# 1_POWER.net
KiCad netlist of a schematic drawn in Altium Designer
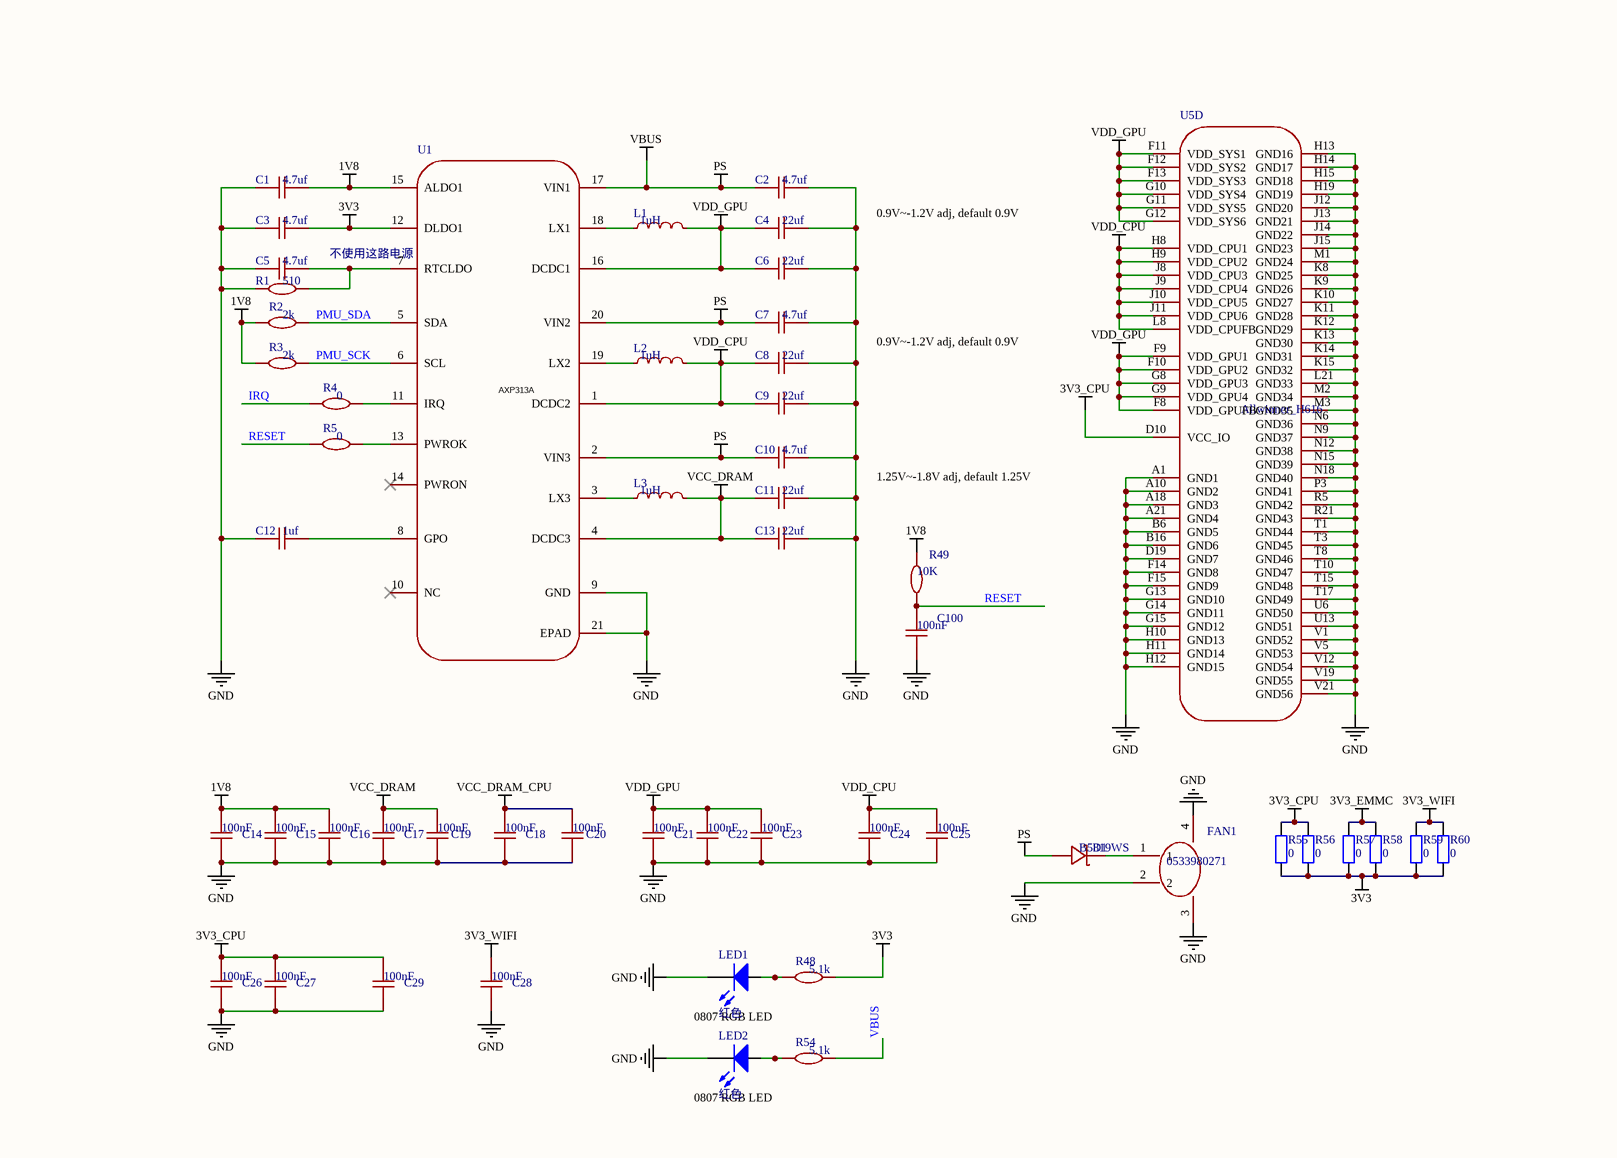
[diagram p0: 1_POWER.schdoc]

(export (version "E")
  (design (tool "Eeschema 10.0.6"))
  (components
    (comp (ref "C1")
      (value "4.7uf")
      (footprint "PCB:C0402")
      (libsource (lib "PCB_Project") (part "CAP_0402"))
    )
    (comp (ref "C2")
      (value "4.7uf")
      (footprint "PCB:C0603")
      (libsource (lib "PCB_Project") (part "CAP_0603"))
    )
    (comp (ref "C3")
      (value "4.7uf")
      (footprint "PCB:C0402")
      (libsource (lib "PCB_Project") (part "CAP_0402"))
    )
    (comp (ref "C4") (value "22uf") (footprint "PCB:C0603") (libsource (lib "PCB_Project") (part "CAP_0603")))
    (comp (ref "C5")
      (value "4.7uf")
      (footprint "PCB:C0402")
      (libsource (lib "PCB_Project") (part "CAP_0402"))
    )
    (comp (ref "C6") (value "22uf") (footprint "PCB:C0603") (libsource (lib "PCB_Project") (part "CAP_0603")))
    (comp (ref "C7")
      (value "4.7uf")
      (footprint "PCB:C0603")
      (libsource (lib "PCB_Project") (part "CAP_0603"))
    )
    (comp (ref "C8") (value "22uf") (footprint "PCB:C0603") (libsource (lib "PCB_Project") (part "CAP_0603")))
    (comp (ref "C9") (value "22uf") (footprint "PCB:C0603") (libsource (lib "PCB_Project") (part "CAP_0603")))
    (comp (ref "C10")
      (value "4.7uf")
      (footprint "PCB:C0603")
      (libsource (lib "PCB_Project") (part "CAP_0603"))
    )
    (comp (ref "C11")
      (value "22uf")
      (footprint "PCB:C0603")
      (libsource (lib "PCB_Project") (part "CAP_0603"))
    )
    (comp (ref "C12") (value "1uf") (footprint "PCB:C0402") (libsource (lib "PCB_Project") (part "CAP_0402")))
    (comp (ref "C13")
      (value "22uf")
      (footprint "PCB:C0603")
      (libsource (lib "PCB_Project") (part "CAP_0603"))
    )
    (comp (ref "C14")
      (value "100nF")
      (footprint "PCB:C0402-NSK")
      (libsource (lib "PCB_Project") (part "CAP_0402"))
    )
    (comp (ref "C15")
      (value "100nF")
      (footprint "PCB:C0402-NSK")
      (libsource (lib "PCB_Project") (part "CAP_0402"))
    )
    (comp (ref "C16")
      (value "100nF")
      (footprint "PCB:C0402-NSK")
      (libsource (lib "PCB_Project") (part "CAP_0402"))
    )
    (comp (ref "C17")
      (value "100nF")
      (footprint "PCB:C0402-NSK")
      (libsource (lib "PCB_Project") (part "CAP_0402"))
    )
    (comp (ref "C18")
      (value "100nF")
      (footprint "PCB:C0402-NSK")
      (libsource (lib "PCB_Project") (part "CAP_0402"))
    )
    (comp (ref "C19")
      (value "100nF")
      (footprint "PCB:C0402-NSK")
      (libsource (lib "PCB_Project") (part "CAP_0402"))
    )
    (comp (ref "C20")
      (value "100nF")
      (footprint "PCB:C0402-NSK")
      (libsource (lib "PCB_Project") (part "CAP_0402"))
    )
    (comp (ref "C21")
      (value "100nF")
      (footprint "PCB:C0402-NSK")
      (libsource (lib "PCB_Project") (part "CAP_0402"))
    )
    (comp (ref "C22")
      (value "100nF")
      (footprint "PCB:C0402-NSK")
      (libsource (lib "PCB_Project") (part "CAP_0402"))
    )
    (comp (ref "C23")
      (value "100nF")
      (footprint "PCB:C0402-NSK")
      (libsource (lib "PCB_Project") (part "CAP_0402"))
    )
    (comp (ref "C24")
      (value "100nF")
      (footprint "PCB:C0402-NSK")
      (libsource (lib "PCB_Project") (part "CAP_0402"))
    )
    (comp (ref "C25")
      (value "100nF")
      (footprint "PCB:C0402-NSK")
      (libsource (lib "PCB_Project") (part "CAP_0402"))
    )
    (comp (ref "C26")
      (value "100nF")
      (footprint "PCB:C0402-NSK")
      (libsource (lib "PCB_Project") (part "CAP_0402"))
    )
    (comp (ref "C27")
      (value "100nF")
      (footprint "PCB:C0402-NSK")
      (libsource (lib "PCB_Project") (part "CAP_0402"))
    )
    (comp (ref "C28")
      (value "100nF")
      (footprint "PCB:C0402-NSK")
      (libsource (lib "PCB_Project") (part "CAP_0402"))
    )
    (comp (ref "C29")
      (value "100nF")
      (footprint "PCB:C0402-NSK")
      (libsource (lib "PCB_Project") (part "CAP_0402"))
    )
    (comp (ref "C100")
      (value "100nF")
      (footprint "PCB:C0402")
      (libsource (lib "PCB_Project") (part "CAP_0402"))
    )
    (comp (ref "D1")
      (value "B5819WS")
      (footprint "PCB:SOD-323_L1.8-W1.3-LS2.5-NSK")
      (libsource (lib "PCB_Project") (part "B5819WS"))
    )
    (comp (ref "FAN1")
      (value "0533980271")
      (footprint "PCB:CONN-SMD_2P-P1.25_053398-0X71")
      (libsource (lib "PCB_Project") (part "0533980271"))
    )
    (comp (ref "L1")
      (value "1uH")
      (footprint "PCB:IND-SMD_L2.0-W1.6_1")
      (libsource (lib "PCB_Project") (part "CKCS201610-2.2uH/M_2"))
    )
    (comp (ref "L2")
      (value "1uH")
      (footprint "PCB:IND-SMD_L2.0-W1.6_1")
      (libsource (lib "PCB_Project") (part "CKCS201610-2.2uH/M_2"))
    )
    (comp (ref "L3")
      (value "1uH")
      (footprint "PCB:IND-SMD_L2.0-W1.6_1")
      (libsource (lib "PCB_Project") (part "CKCS201610-2.2uH/M_2"))
    )
    (comp (ref "LED1")
      (value "红色")
      (footprint "PCB:LED0805_G")
      (description "贴片LED")
      (libsource (lib "PCB_Project") (part "LED"))
    )
    (comp (ref "LED2")
      (value "红色")
      (footprint "PCB:LED0805_G")
      (description "贴片LED")
      (libsource (lib "PCB_Project") (part "LED"))
    )
    (comp (ref "R1")
      (value "510")
      (footprint "PCB:R0402-NSK_2")
      (libsource (lib "PCB_Project") (part "Res_0402"))
    )
    (comp (ref "R2")
      (value "2k")
      (footprint "PCB:R0402-NSK_2")
      (libsource (lib "PCB_Project") (part "Res_0402"))
    )
    (comp (ref "R3")
      (value "2k")
      (footprint "PCB:R0402-NSK_2")
      (libsource (lib "PCB_Project") (part "Res_0402"))
    )
    (comp (ref "R4")
      (value "0")
      (footprint "PCB:R0402-NSK_2")
      (libsource (lib "PCB_Project") (part "Res_0402"))
    )
    (comp (ref "R5")
      (value "0")
      (footprint "PCB:R0402-NSK_2")
      (libsource (lib "PCB_Project") (part "Res_0402"))
    )
    (comp (ref "R48")
      (value "5.1k")
      (footprint "PCB:R0402-NSK_2")
      (libsource (lib "PCB_Project") (part "Res_0402"))
    )
    (comp (ref "R49")
      (value "10K")
      (footprint "PCB:R0402-NSK_2")
      (libsource (lib "PCB_Project") (part "Res_0402"))
    )
    (comp (ref "R54")
      (value "5.1k")
      (footprint "PCB:R0402-NSK_2")
      (libsource (lib "PCB_Project") (part "Res_0402"))
    )
    (comp (ref "R55")
      (value "0")
      (footprint "PCB:R0805_L")
      (description "贴片电阻")
      (libsource (lib "PCB_Project") (part "R"))
    )
    (comp (ref "R56")
      (value "0")
      (footprint "PCB:R0805_L")
      (description "贴片电阻")
      (libsource (lib "PCB_Project") (part "R"))
    )
    (comp (ref "R57")
      (value "0")
      (footprint "PCB:R0805_L")
      (description "贴片电阻")
      (libsource (lib "PCB_Project") (part "R"))
    )
    (comp (ref "R58")
      (value "0")
      (footprint "PCB:R0805_L")
      (description "贴片电阻")
      (libsource (lib "PCB_Project") (part "R"))
    )
    (comp (ref "R59")
      (value "0")
      (footprint "PCB:R0805_L")
      (description "贴片电阻")
      (libsource (lib "PCB_Project") (part "R"))
    )
    (comp (ref "R60")
      (value "0")
      (footprint "PCB:R0805_L")
      (description "贴片电阻")
      (libsource (lib "PCB_Project") (part "R"))
    )
    (comp (ref "U1")
      (value "AXP313A")
      (footprint "PCB:WQFN-20_L3.0-W3.0-P0.40-BL-EP")
      (libsource (lib "PCB_Project") (part "AXP1530"))
    )
    (comp (ref "U5")
      (value "Allwinner_H616")
      (footprint "PCB:BGA284P65B1200_1400H125")
      (libsource (lib "PCB_Project") (part "Allwinner_H616"))
    )
  )
  (nets
    (net (code "1") (name "/IRQ") (class "Default")
      (node (ref "R4") (pin "1") (pinfunction "1_1") (pintype "passive"))
    )
    (net (code "2") (name "/PMU_SCK") (class "Default")
      (node (ref "R3") (pin "2") (pinfunction "2_2") (pintype "passive"))
      (node (ref "U1") (pin "6") (pinfunction "SCL_6") (pintype "passive"))
    )
    (net (code "3") (name "/PMU_SDA") (class "Default")
      (node (ref "R2") (pin "2") (pinfunction "2_2") (pintype "passive"))
      (node (ref "U1") (pin "5") (pinfunction "SDA_5") (pintype "passive"))
    )
    (net (code "4") (name "/RESET") (class "Default")
      (node (ref "C100") (pin "2") (pinfunction "2_2") (pintype "passive"))
      (node (ref "R49") (pin "1") (pinfunction "1_1") (pintype "passive"))
      (node (ref "R5") (pin "1") (pinfunction "1_1") (pintype "passive"))
    )
    (net (code "5") (name "1V8") (class "Default")
      (node (ref "C1") (pin "2") (pinfunction "2_2") (pintype "passive"))
      (node (ref "C14") (pin "2") (pinfunction "2_2") (pintype "passive"))
      (node (ref "C15") (pin "2") (pinfunction "2_2") (pintype "passive"))
      (node (ref "C16") (pin "2") (pinfunction "2_2") (pintype "passive"))
      (node (ref "R2") (pin "1") (pinfunction "1_1") (pintype "passive"))
      (node (ref "R3") (pin "1") (pinfunction "1_1") (pintype "passive"))
      (node (ref "R49") (pin "2") (pinfunction "2_2") (pintype "passive"))
      (node (ref "U1") (pin "15") (pinfunction "ALDO1_15") (pintype "passive"))
    )
    (net (code "6") (name "3V3") (class "Default")
      (node (ref "C3") (pin "2") (pinfunction "2_2") (pintype "passive"))
      (node (ref "R48") (pin "2") (pinfunction "2_2") (pintype "passive"))
      (node (ref "R55") (pin "1") (pinfunction "1_1") (pintype "passive"))
      (node (ref "R56") (pin "1") (pinfunction "1_1") (pintype "passive"))
      (node (ref "R57") (pin "1") (pinfunction "1_1") (pintype "passive"))
      (node (ref "R58") (pin "1") (pinfunction "1_1") (pintype "passive"))
      (node (ref "R59") (pin "1") (pinfunction "1_1") (pintype "passive"))
      (node (ref "R60") (pin "1") (pinfunction "1_1") (pintype "passive"))
      (node (ref "U1") (pin "12") (pinfunction "DLDO1_12") (pintype "passive"))
    )
    (net (code "7") (name "3V3_CPU") (class "Default")
      (node (ref "C26") (pin "2") (pinfunction "2_2") (pintype "passive"))
      (node (ref "C27") (pin "2") (pinfunction "2_2") (pintype "passive"))
      (node (ref "C29") (pin "2") (pinfunction "2_2") (pintype "passive"))
      (node (ref "R55") (pin "2") (pinfunction "2_2") (pintype "passive"))
      (node (ref "R56") (pin "2") (pinfunction "2_2") (pintype "passive"))
      (node (ref "U5") (pin "D10") (pinfunction "VCC_IO_D10") (pintype "passive"))
    )
    (net (code "8") (name "3V3_EMMC") (class "Default")
      (node (ref "R57") (pin "2") (pinfunction "2_2") (pintype "passive"))
      (node (ref "R58") (pin "2") (pinfunction "2_2") (pintype "passive"))
    )
    (net (code "9") (name "3V3_WIFI") (class "Default")
      (node (ref "C28") (pin "2") (pinfunction "2_2") (pintype "passive"))
      (node (ref "R59") (pin "2") (pinfunction "2_2") (pintype "passive"))
      (node (ref "R60") (pin "2") (pinfunction "2_2") (pintype "passive"))
    )
    (net (code "10") (name "GND") (class "Default")
      (node (ref "C1") (pin "1") (pinfunction "1_1") (pintype "passive"))
      (node (ref "C10") (pin "2") (pinfunction "2_2") (pintype "passive"))
      (node (ref "C100") (pin "1") (pinfunction "1_1") (pintype "passive"))
      (node (ref "C11") (pin "2") (pinfunction "2_2") (pintype "passive"))
      (node (ref "C12") (pin "1") (pinfunction "1_1") (pintype "passive"))
      (node (ref "C13") (pin "2") (pinfunction "2_2") (pintype "passive"))
      (node (ref "C14") (pin "1") (pinfunction "1_1") (pintype "passive"))
      (node (ref "C15") (pin "1") (pinfunction "1_1") (pintype "passive"))
      (node (ref "C16") (pin "1") (pinfunction "1_1") (pintype "passive"))
      (node (ref "C17") (pin "1") (pinfunction "1_1") (pintype "passive"))
      (node (ref "C18") (pin "1") (pinfunction "1_1") (pintype "passive"))
      (node (ref "C19") (pin "1") (pinfunction "1_1") (pintype "passive"))
      (node (ref "C2") (pin "2") (pinfunction "2_2") (pintype "passive"))
      (node (ref "C20") (pin "1") (pinfunction "1_1") (pintype "passive"))
      (node (ref "C21") (pin "1") (pinfunction "1_1") (pintype "passive"))
      (node (ref "C22") (pin "1") (pinfunction "1_1") (pintype "passive"))
      (node (ref "C23") (pin "1") (pinfunction "1_1") (pintype "passive"))
      (node (ref "C24") (pin "1") (pinfunction "1_1") (pintype "passive"))
      (node (ref "C25") (pin "1") (pinfunction "1_1") (pintype "passive"))
      (node (ref "C26") (pin "1") (pinfunction "1_1") (pintype "passive"))
      (node (ref "C27") (pin "1") (pinfunction "1_1") (pintype "passive"))
      (node (ref "C28") (pin "1") (pinfunction "1_1") (pintype "passive"))
      (node (ref "C29") (pin "1") (pinfunction "1_1") (pintype "passive"))
      (node (ref "C3") (pin "1") (pinfunction "1_1") (pintype "passive"))
      (node (ref "C4") (pin "2") (pinfunction "2_2") (pintype "passive"))
      (node (ref "C5") (pin "1") (pinfunction "1_1") (pintype "passive"))
      (node (ref "C6") (pin "2") (pinfunction "2_2") (pintype "passive"))
      (node (ref "C7") (pin "2") (pinfunction "2_2") (pintype "passive"))
      (node (ref "C8") (pin "2") (pinfunction "2_2") (pintype "passive"))
      (node (ref "C9") (pin "2") (pinfunction "2_2") (pintype "passive"))
      (node (ref "FAN1") (pin "2") (pinfunction "2_2") (pintype "passive"))
      (node (ref "FAN1") (pin "3") (pinfunction "3_3") (pintype "passive"))
      (node (ref "FAN1") (pin "4") (pinfunction "4_4") (pintype "passive"))
      (node (ref "LED1") (pin "2") (pinfunction "K_2") (pintype "passive"))
      (node (ref "LED2") (pin "2") (pinfunction "K_2") (pintype "passive"))
      (node (ref "R1") (pin "1") (pinfunction "1_1") (pintype "passive"))
      (node (ref "U1") (pin "21") (pinfunction "EPAD_21") (pintype "passive"))
      (node (ref "U1") (pin "9") (pinfunction "GND_9") (pintype "passive"))
      (node (ref "U5") (pin "A1") (pinfunction "GND1_A1") (pintype "passive"))
      (node (ref "U5") (pin "A10") (pinfunction "GND2_A10") (pintype "passive"))
      (node (ref "U5") (pin "A18") (pinfunction "GND3_A18") (pintype "passive"))
      (node (ref "U5") (pin "A21") (pinfunction "GND4_A21") (pintype "passive"))
      (node (ref "U5") (pin "B16") (pinfunction "GND6_B16") (pintype "passive"))
      (node (ref "U5") (pin "B6") (pinfunction "GND5_B6") (pintype "passive"))
      (node (ref "U5") (pin "D19") (pinfunction "GND7_D19") (pintype "passive"))
      (node (ref "U5") (pin "F14") (pinfunction "GND8_F14") (pintype "passive"))
      (node (ref "U5") (pin "F15") (pinfunction "GND9_F15") (pintype "passive"))
      (node (ref "U5") (pin "G13") (pinfunction "GND10_G13") (pintype "passive"))
      (node (ref "U5") (pin "G14") (pinfunction "GND11_G14") (pintype "passive"))
      (node (ref "U5") (pin "G15") (pinfunction "GND12_G15") (pintype "passive"))
      (node (ref "U5") (pin "H10") (pinfunction "GND13_H10") (pintype "passive"))
      (node (ref "U5") (pin "H11") (pinfunction "GND14_H11") (pintype "passive"))
      (node (ref "U5") (pin "H12") (pinfunction "GND15_H12") (pintype "passive"))
      (node (ref "U5") (pin "H13") (pinfunction "GND16_H13") (pintype "passive"))
      (node (ref "U5") (pin "H14") (pinfunction "GND17_H14") (pintype "passive"))
      (node (ref "U5") (pin "H15") (pinfunction "GND18_H15") (pintype "passive"))
      (node (ref "U5") (pin "H19") (pinfunction "GND19_H19") (pintype "passive"))
      (node (ref "U5") (pin "J12") (pinfunction "GND20_J12") (pintype "passive"))
      (node (ref "U5") (pin "J13") (pinfunction "GND21_J13") (pintype "passive"))
      (node (ref "U5") (pin "J14") (pinfunction "GND22_J14") (pintype "passive"))
      (node (ref "U5") (pin "J15") (pinfunction "GND23_J15") (pintype "passive"))
      (node (ref "U5") (pin "K10") (pinfunction "GND27_K10") (pintype "passive"))
      (node (ref "U5") (pin "K11") (pinfunction "GND28_K11") (pintype "passive"))
      (node (ref "U5") (pin "K12") (pinfunction "GND29_K12") (pintype "passive"))
      (node (ref "U5") (pin "K13") (pinfunction "GND30_K13") (pintype "passive"))
      (node (ref "U5") (pin "K14") (pinfunction "GND31_K14") (pintype "passive"))
      (node (ref "U5") (pin "K15") (pinfunction "GND32_K15") (pintype "passive"))
      (node (ref "U5") (pin "K8") (pinfunction "GND25_K8") (pintype "passive"))
      (node (ref "U5") (pin "K9") (pinfunction "GND26_K9") (pintype "passive"))
      (node (ref "U5") (pin "L21") (pinfunction "GND33_L21") (pintype "passive"))
      (node (ref "U5") (pin "M1") (pinfunction "GND24_M1") (pintype "passive"))
      (node (ref "U5") (pin "M2") (pinfunction "GND34_M2") (pintype "passive"))
      (node (ref "U5") (pin "M3") (pinfunction "GND35_M3") (pintype "passive"))
      (node (ref "U5") (pin "N12") (pinfunction "GND38_N12") (pintype "passive"))
      (node (ref "U5") (pin "N15") (pinfunction "GND39_N15") (pintype "passive"))
      (node (ref "U5") (pin "N18") (pinfunction "GND40_N18") (pintype "passive"))
      (node (ref "U5") (pin "N6") (pinfunction "GND36_N6") (pintype "passive"))
      (node (ref "U5") (pin "N9") (pinfunction "GND37_N9") (pintype "passive"))
      (node (ref "U5") (pin "P3") (pinfunction "GND41_P3") (pintype "passive"))
      (node (ref "U5") (pin "R21") (pinfunction "GND43_R21") (pintype "passive"))
      (node (ref "U5") (pin "R5") (pinfunction "GND42_R5") (pintype "passive"))
      (node (ref "U5") (pin "T1") (pinfunction "GND44_T1") (pintype "passive"))
      (node (ref "U5") (pin "T10") (pinfunction "GND47_T10") (pintype "passive"))
      (node (ref "U5") (pin "T15") (pinfunction "GND48_T15") (pintype "passive"))
      (node (ref "U5") (pin "T17") (pinfunction "GND49_T17") (pintype "passive"))
      (node (ref "U5") (pin "T3") (pinfunction "GND45_T3") (pintype "passive"))
      (node (ref "U5") (pin "T8") (pinfunction "GND46_T8") (pintype "passive"))
      (node (ref "U5") (pin "U13") (pinfunction "GND51_U13") (pintype "passive"))
      (node (ref "U5") (pin "U6") (pinfunction "GND50_U6") (pintype "passive"))
      (node (ref "U5") (pin "V1") (pinfunction "GND52_V1") (pintype "passive"))
      (node (ref "U5") (pin "V12") (pinfunction "GND54_V12") (pintype "passive"))
      (node (ref "U5") (pin "V19") (pinfunction "GND55_V19") (pintype "passive"))
      (node (ref "U5") (pin "V21") (pinfunction "GND56_V21") (pintype "passive"))
      (node (ref "U5") (pin "V5") (pinfunction "GND53_V5") (pintype "passive"))
    )
    (net (code "11") (name "Net-(D1-K)") (class "Default")
      (node (ref "D1") (pin "1") (pinfunction "K_1") (pintype "passive"))
      (node (ref "FAN1") (pin "1") (pinfunction "1_1") (pintype "passive"))
    )
    (net (code "12") (name "Net-(LED1-A)") (class "Default")
      (node (ref "LED1") (pin "1") (pinfunction "A_1") (pintype "passive"))
      (node (ref "R48") (pin "1") (pinfunction "1_1") (pintype "passive"))
    )
    (net (code "13") (name "Net-(LED2-A)") (class "Default")
      (node (ref "LED2") (pin "1") (pinfunction "A_1") (pintype "passive"))
      (node (ref "R54") (pin "1") (pinfunction "1_1") (pintype "passive"))
    )
    (net (code "14") (name "Net-(U1-GPO)") (class "Default")
      (node (ref "C12") (pin "2") (pinfunction "2_2") (pintype "passive"))
      (node (ref "U1") (pin "8") (pinfunction "GPO_8") (pintype "passive"))
    )
    (net (code "15") (name "Net-(U1-IRQ)") (class "Default")
      (node (ref "R4") (pin "2") (pinfunction "2_2") (pintype "passive"))
      (node (ref "U1") (pin "11") (pinfunction "IRQ_11") (pintype "passive"))
    )
    (net (code "16") (name "Net-(U1-LX1)") (class "Default")
      (node (ref "L1") (pin "1") (pinfunction "1_1") (pintype "passive"))
      (node (ref "U1") (pin "18") (pinfunction "LX1_18") (pintype "passive"))
    )
    (net (code "17") (name "Net-(U1-LX2)") (class "Default")
      (node (ref "L2") (pin "1") (pinfunction "1_1") (pintype "passive"))
      (node (ref "U1") (pin "19") (pinfunction "LX2_19") (pintype "passive"))
    )
    (net (code "18") (name "Net-(U1-LX3)") (class "Default")
      (node (ref "L3") (pin "1") (pinfunction "1_1") (pintype "passive"))
      (node (ref "U1") (pin "3") (pinfunction "LX3_3") (pintype "passive"))
    )
    (net (code "19") (name "Net-(U1-PWROK)") (class "Default")
      (node (ref "R5") (pin "2") (pinfunction "2_2") (pintype "passive"))
      (node (ref "U1") (pin "13") (pinfunction "PWROK_13") (pintype "passive"))
    )
    (net (code "20") (name "Net-(U1-RTCLDO)") (class "Default")
      (node (ref "C5") (pin "2") (pinfunction "2_2") (pintype "passive"))
      (node (ref "R1") (pin "2") (pinfunction "2_2") (pintype "passive"))
      (node (ref "U1") (pin "7") (pinfunction "RTCLDO_7") (pintype "passive"))
    )
    (net (code "21") (name "PS") (class "Default")
      (node (ref "C10") (pin "1") (pinfunction "1_1") (pintype "passive"))
      (node (ref "C2") (pin "1") (pinfunction "1_1") (pintype "passive"))
      (node (ref "C7") (pin "1") (pinfunction "1_1") (pintype "passive"))
      (node (ref "D1") (pin "2") (pinfunction "A_2") (pintype "passive"))
      (node (ref "R54") (pin "2") (pinfunction "2_2") (pintype "passive"))
      (node (ref "U1") (pin "17") (pinfunction "VIN1_17") (pintype "passive"))
      (node (ref "U1") (pin "2") (pinfunction "VIN3_2") (pintype "passive"))
      (node (ref "U1") (pin "20") (pinfunction "VIN2_20") (pintype "passive"))
    )
    (net (code "22") (name "VCC_DRAM") (class "Default")
      (node (ref "C11") (pin "1") (pinfunction "1_1") (pintype "passive"))
      (node (ref "C13") (pin "1") (pinfunction "1_1") (pintype "passive"))
      (node (ref "C17") (pin "2") (pinfunction "2_2") (pintype "passive"))
      (node (ref "C19") (pin "2") (pinfunction "2_2") (pintype "passive"))
      (node (ref "L3") (pin "2") (pinfunction "2_2") (pintype "passive"))
      (node (ref "U1") (pin "4") (pinfunction "DCDC3_4") (pintype "passive"))
    )
    (net (code "23") (name "VCC_DRAM_CPU") (class "Default")
      (node (ref "C18") (pin "2") (pinfunction "2_2") (pintype "passive"))
      (node (ref "C20") (pin "2") (pinfunction "2_2") (pintype "passive"))
    )
    (net (code "24") (name "VDD_CPU") (class "Default")
      (node (ref "C24") (pin "2") (pinfunction "2_2") (pintype "passive"))
      (node (ref "C25") (pin "2") (pinfunction "2_2") (pintype "passive"))
      (node (ref "C8") (pin "1") (pinfunction "1_1") (pintype "passive"))
      (node (ref "C9") (pin "1") (pinfunction "1_1") (pintype "passive"))
      (node (ref "L2") (pin "2") (pinfunction "2_2") (pintype "passive"))
      (node (ref "U1") (pin "1") (pinfunction "DCDC2_1") (pintype "passive"))
      (node (ref "U5") (pin "H8") (pinfunction "VDD_CPU1_H8") (pintype "passive"))
      (node (ref "U5") (pin "H9") (pinfunction "VDD_CPU2_H9") (pintype "passive"))
      (node (ref "U5") (pin "J10") (pinfunction "VDD_CPU5_J10") (pintype "passive"))
      (node (ref "U5") (pin "J11") (pinfunction "VDD_CPU6_J11") (pintype "passive"))
      (node (ref "U5") (pin "J8") (pinfunction "VDD_CPU3_J8") (pintype "passive"))
      (node (ref "U5") (pin "J9") (pinfunction "VDD_CPU4_J9") (pintype "passive"))
      (node (ref "U5") (pin "L8") (pinfunction "VDD_CPUFB_L8") (pintype "passive"))
    )
    (net (code "25") (name "VDD_GPU") (class "Default")
      (node (ref "C21") (pin "2") (pinfunction "2_2") (pintype "passive"))
      (node (ref "C22") (pin "2") (pinfunction "2_2") (pintype "passive"))
      (node (ref "C23") (pin "2") (pinfunction "2_2") (pintype "passive"))
      (node (ref "C4") (pin "1") (pinfunction "1_1") (pintype "passive"))
      (node (ref "C6") (pin "1") (pinfunction "1_1") (pintype "passive"))
      (node (ref "L1") (pin "2") (pinfunction "2_2") (pintype "passive"))
      (node (ref "U1") (pin "16") (pinfunction "DCDC1_16") (pintype "passive"))
      (node (ref "U5") (pin "F10") (pinfunction "VDD_GPU2_F10") (pintype "passive"))
      (node (ref "U5") (pin "F11") (pinfunction "VDD_SYS1_F11") (pintype "passive"))
      (node (ref "U5") (pin "F12") (pinfunction "VDD_SYS2_F12") (pintype "passive"))
      (node (ref "U5") (pin "F13") (pinfunction "VDD_SYS3_F13") (pintype "passive"))
      (node (ref "U5") (pin "F8") (pinfunction "VDD_GPUFB_F8") (pintype "passive"))
      (node (ref "U5") (pin "F9") (pinfunction "VDD_GPU1_F9") (pintype "passive"))
      (node (ref "U5") (pin "G10") (pinfunction "VDD_SYS4_G10") (pintype "passive"))
      (node (ref "U5") (pin "G11") (pinfunction "VDD_SYS5_G11") (pintype "passive"))
      (node (ref "U5") (pin "G12") (pinfunction "VDD_SYS6_G12") (pintype "passive"))
      (node (ref "U5") (pin "G8") (pinfunction "VDD_GPU3_G8") (pintype "passive"))
      (node (ref "U5") (pin "G9") (pinfunction "VDD_GPU4_G9") (pintype "passive"))
    )
    (net (code "26") (name "unconnected-(U1-NC-Pad10)") (class "Default")
      (node (ref "U1") (pin "10") (pinfunction "NC_10") (pintype "passive+no_connect"))
    )
    (net (code "27") (name "unconnected-(U1-PWRON-Pad14)") (class "Default")
      (node (ref "U1") (pin "14") (pinfunction "PWRON_14") (pintype "passive+no_connect"))
    )
  )
)
